# untitled.net
KiCad netlist of a schematic drawn in EAGLE
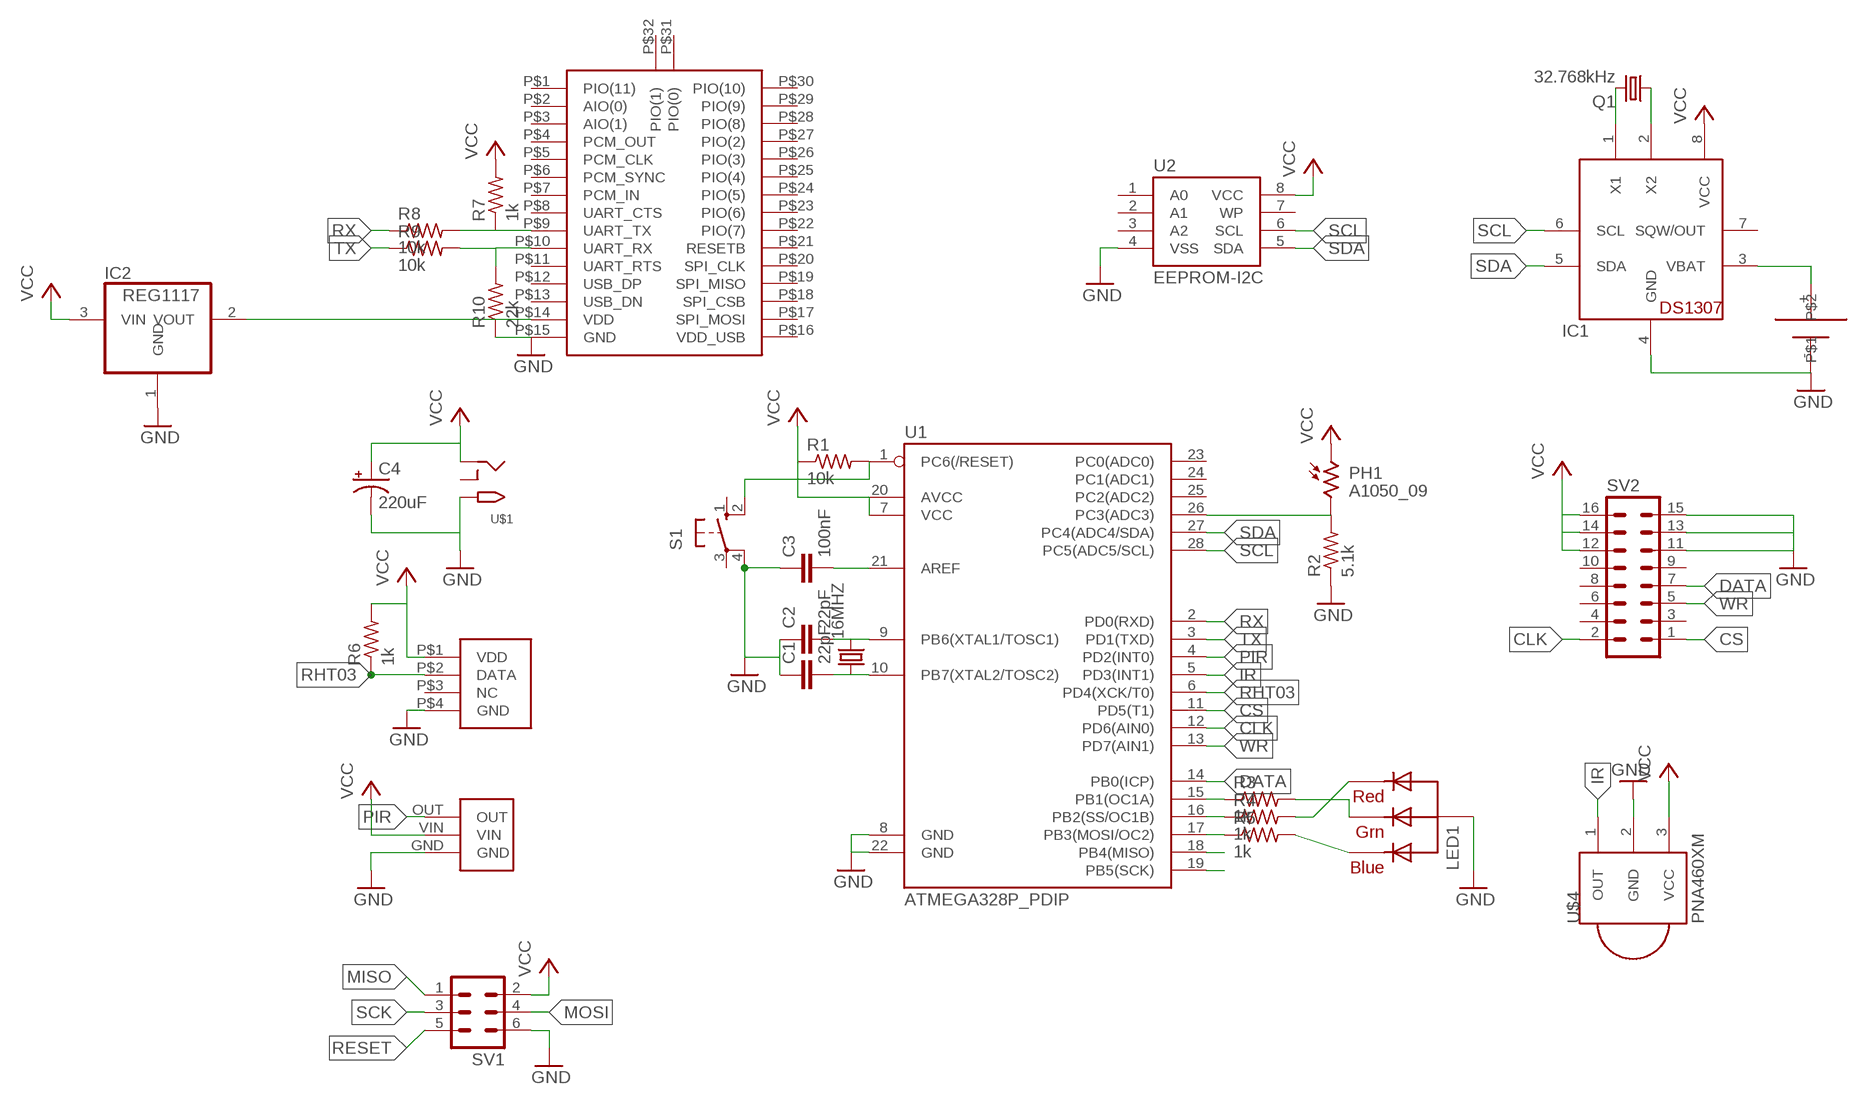
[diagram p0: schematic, sheet 1]

(export (version "E")
  (design (tool "Eeschema 10.0.6"))
  (components
    (comp (ref "16MHZ")
      (value "CRYSTALHC49U-H")
      (footprint "eagle-import:HC49U-H")
      (libsource (lib "eagle-import") (part "CRYSTALHC49U-H"))
    )
    (comp (ref "C1")
      (value "22pF")
      (footprint "eagle-import:C025-024X044")
      (libsource (lib "eagle-import") (part "C-EU025-024X044"))
    )
    (comp (ref "C2")
      (value "22pF")
      (footprint "eagle-import:C025-024X044")
      (libsource (lib "eagle-import") (part "C-EU025-024X044"))
    )
    (comp (ref "C3")
      (value "100nF")
      (footprint "eagle-import:C025-024X044")
      (libsource (lib "eagle-import") (part "C-EU025-024X044"))
    )
    (comp (ref "C4")
      (value "220uF")
      (footprint "eagle-import:E3,5-8")
      (libsource (lib "eagle-import") (part "CPOL-USE3.5-8"))
    )
    (comp (ref "IC1")
      (value "DS1307")
      (footprint "eagle-import:DIL08")
      (libsource (lib "eagle-import") (part "DS1307"))
    )
    (comp (ref "IC2")
      (value "REG1117")
      (footprint "eagle-import:SOT223")
      (libsource (lib "eagle-import") (part "REG1117"))
    )
    (comp (ref "LED1")
      (value "RGBLED_CA-5MM")
      (footprint "eagle-import:LED5MMRGB")
      (libsource (lib "eagle-import") (part "RGBLED_CA-5MM"))
    )
    (comp (ref "PH1")
      (value "A1050_09")
      (footprint "eagle-import:T0-46-A10XX")
      (libsource (lib "eagle-import") (part "A1050_09"))
    )
    (comp (ref "Q1")
      (value "32.768kHz")
      (footprint "eagle-import:TC38H")
      (libsource (lib "eagle-import") (part "CRYSTALTC38H"))
    )
    (comp (ref "R1")
      (value "10k")
      (footprint "eagle-import:0207_10")
      (libsource (lib "eagle-import") (part "R-US_0207/10"))
    )
    (comp (ref "R2")
      (value "5.1k")
      (footprint "eagle-import:0207_10")
      (libsource (lib "eagle-import") (part "R-US_0207/10"))
    )
    (comp (ref "R3")
      (value "1k")
      (footprint "eagle-import:0207_10")
      (libsource (lib "eagle-import") (part "R-US_0207/10"))
    )
    (comp (ref "R4")
      (value "1k")
      (footprint "eagle-import:0207_10")
      (libsource (lib "eagle-import") (part "R-US_0207/10"))
    )
    (comp (ref "R5")
      (value "1k")
      (footprint "eagle-import:0207_10")
      (libsource (lib "eagle-import") (part "R-US_0207/10"))
    )
    (comp (ref "R6")
      (value "1k")
      (footprint "eagle-import:0207_10")
      (libsource (lib "eagle-import") (part "R-US_0207/10"))
    )
    (comp (ref "R7")
      (value "1k")
      (footprint "eagle-import:0207_10")
      (libsource (lib "eagle-import") (part "R-US_0207/10"))
    )
    (comp (ref "R8")
      (value "10k")
      (footprint "eagle-import:0207_10")
      (libsource (lib "eagle-import") (part "R-US_0207/10"))
    )
    (comp (ref "R9")
      (value "10k")
      (footprint "eagle-import:0207_10")
      (libsource (lib "eagle-import") (part "R-US_0207/10"))
    )
    (comp (ref "R10")
      (value "22k")
      (footprint "eagle-import:0207_10")
      (libsource (lib "eagle-import") (part "R-US_0207/10"))
    )
    (comp (ref "S1")
      (value "10-XX")
      (footprint "eagle-import:B3F-10XX")
      (fields (field (name "MPN") "B3F-1000"))
      (libsource (lib "eagle-import") (part "10-XX"))
    )
    (comp (ref "SV1")
      (value "ML6")
      (footprint "eagle-import:ML6")
      (libsource (lib "eagle-import") (part "ML6"))
    )
    (comp (ref "SV2")
      (value "ML16")
      (footprint "eagle-import:ML16")
      (libsource (lib "eagle-import") (part "ML16"))
    )
    (comp (ref "U$1")
      (value "2.1MMJACK")
      (footprint "eagle-import:2.1MMJACK_BREADBOARD")
      (libsource (lib "eagle-import") (part "2.1MMJACK"))
    )
    (comp (ref "U$2")
      (value "RHT03THROUGH_HOLE")
      (footprint "eagle-import:RHT03")
      (libsource (lib "eagle-import") (part "RHT03THROUGH_HOLE"))
    )
    (comp (ref "U$3")
      (value "PIR_PM-6")
      (footprint "eagle-import:PIR_THROUGHHOLE")
      (libsource (lib "eagle-import") (part "PIR_PM-6"))
    )
    (comp (ref "U$4")
      (value "PNA460XM")
      (footprint "eagle-import:PNA460XM")
      (libsource (lib "eagle-import") (part "PNA460XM"))
    )
    (comp (ref "U$5")
      (value "CR2032")
      (footprint "eagle-import:CR2032-THM")
      (libsource (lib "eagle-import") (part "CR2032"))
    )
    (comp (ref "U$6")
      (value "BTM-182")
      (footprint "eagle-import:BTM-182")
      (libsource (lib "eagle-import") (part "BTM-182"))
    )
    (comp (ref "U1")
      (value "ATMEGA328P_PDIP")
      (footprint "eagle-import:DIL28-3")
      (libsource (lib "eagle-import") (part "ATMEGA328P_PDIP"))
    )
    (comp (ref "U2")
      (value "EEPROM-I2C")
      (footprint "eagle-import:DIL08")
      (libsource (lib "eagle-import") (part "EEPROM-I2C"))
    )
  )
  (nets
    (net (code "1") (name "CLK") (class "Default")
      (node (ref "SV2") (pin "2") (pinfunction "2_2") (pintype "passive"))
      (node (ref "U1") (pin "12") (pinfunction "PD6(AIN0)_12") (pintype "bidirectional"))
    )
    (net (code "2") (name "CS") (class "Default")
      (node (ref "SV2") (pin "1") (pinfunction "1_1") (pintype "passive"))
      (node (ref "U1") (pin "11") (pinfunction "PD5(T1)_11") (pintype "bidirectional"))
    )
    (net (code "3") (name "DATA") (class "Default")
      (node (ref "SV2") (pin "7") (pinfunction "7_7") (pintype "passive"))
      (node (ref "U1") (pin "14") (pinfunction "PB0(ICP)_14") (pintype "bidirectional"))
    )
    (net (code "4") (name "GND") (class "Default")
      (node (ref "C1") (pin "1") (pinfunction "1_1") (pintype "passive"))
      (node (ref "C2") (pin "1") (pinfunction "1_1") (pintype "passive"))
      (node (ref "C3") (pin "1") (pinfunction "1_1") (pintype "passive"))
      (node (ref "C4") (pin "-") (pinfunction "-_-") (pintype "passive"))
      (node (ref "IC1") (pin "4") (pinfunction "GND_4") (pintype "power_in"))
      (node (ref "IC2") (pin "1") (pinfunction "GND_1") (pintype "power_in"))
      (node (ref "LED1") (pin "2") (pinfunction "VCC_2") (pintype "bidirectional"))
      (node (ref "R10") (pin "1") (pinfunction "1_1") (pintype "passive"))
      (node (ref "R2") (pin "1") (pinfunction "1_1") (pintype "passive"))
      (node (ref "S1") (pin "4") (pinfunction "P1_4") (pintype "passive"))
      (node (ref "SV1") (pin "6") (pinfunction "6_6") (pintype "passive"))
      (node (ref "SV2") (pin "11") (pinfunction "11_11") (pintype "passive"))
      (node (ref "SV2") (pin "13") (pinfunction "13_13") (pintype "passive"))
      (node (ref "SV2") (pin "15") (pinfunction "15_15") (pintype "passive"))
      (node (ref "U$1") (pin "GND") (pinfunction "TIP_GND") (pintype "bidirectional"))
      (node (ref "U$2") (pin "P$4") (pinfunction "GND_P$4") (pintype "bidirectional"))
      (node (ref "U$3") (pin "GND") (pinfunction "GND_GND") (pintype "bidirectional"))
      (node (ref "U$4") (pin "2") (pinfunction "GND_2") (pintype "power_in"))
      (node (ref "U$5") (pin "-") (pinfunction "P$2_-") (pintype "bidirectional"))
      (node (ref "U$6") (pin "P$15") (pinfunction "GND_P$15") (pintype "bidirectional"))
      (node (ref "U1") (pin "22") (pinfunction "GND_22") (pintype "bidirectional"))
      (node (ref "U1") (pin "8") (pinfunction "GND_8") (pintype "bidirectional"))
      (node (ref "U2") (pin "4") (pinfunction "VSS_4") (pintype "power_in"))
    )
    (net (code "5") (name "IR") (class "Default")
      (node (ref "U$4") (pin "1") (pinfunction "OUT_1") (pintype "output"))
      (node (ref "U1") (pin "5") (pinfunction "PD3(INT1)_5") (pintype "bidirectional"))
    )
    (net (code "6") (name "MISO") (class "Default")
      (node (ref "SV1") (pin "1") (pinfunction "1_1") (pintype "passive"))
      (node (ref "U1") (pin "18") (pinfunction "PB4(MISO)_18") (pintype "bidirectional"))
    )
    (net (code "7") (name "MOSI") (class "Default")
      (node (ref "R5") (pin "1") (pinfunction "1_1") (pintype "passive"))
      (node (ref "SV1") (pin "4") (pinfunction "4_4") (pintype "passive"))
      (node (ref "U1") (pin "17") (pinfunction "PB3(MOSI/OC2)_17") (pintype "bidirectional"))
    )
    (net (code "8") (name "Net-(IC1-VBAT)") (class "Default")
      (node (ref "IC1") (pin "3") (pinfunction "VBAT_3") (pintype "power_in"))
      (node (ref "U$5") (pin "+") (pinfunction "P$1_+") (pintype "bidirectional"))
    )
    (net (code "9") (name "Net-(IC1-X1)") (class "Default")
      (node (ref "IC1") (pin "1") (pinfunction "X1_1") (pintype "passive"))
      (node (ref "Q1") (pin "2") (pinfunction "2_2") (pintype "passive"))
    )
    (net (code "10") (name "Net-(IC1-X2)") (class "Default")
      (node (ref "IC1") (pin "2") (pinfunction "X2_2") (pintype "passive"))
      (node (ref "Q1") (pin "1") (pinfunction "1_1") (pintype "passive"))
    )
    (net (code "11") (name "Net-(IC2-VOUT)") (class "Default")
      (node (ref "IC2") (pin "2") (pinfunction "VOUT_2") (pintype "output"))
      (node (ref "U$6") (pin "P$14") (pinfunction "VDD_P$14") (pintype "bidirectional"))
    )
    (net (code "12") (name "Net-(LED1-BLUE)") (class "Default")
      (node (ref "LED1") (pin "4") (pinfunction "BLUE_4") (pintype "bidirectional"))
      (node (ref "R5") (pin "2") (pinfunction "2_2") (pintype "passive"))
    )
    (net (code "13") (name "Net-(LED1-GREEN)") (class "Default")
      (node (ref "LED1") (pin "3") (pinfunction "GREEN_3") (pintype "bidirectional"))
      (node (ref "R3") (pin "2") (pinfunction "2_2") (pintype "passive"))
    )
    (net (code "14") (name "Net-(LED1-RED)") (class "Default")
      (node (ref "LED1") (pin "1") (pinfunction "RED_1") (pintype "bidirectional"))
      (node (ref "R4") (pin "2") (pinfunction "2_2") (pintype "passive"))
    )
    (net (code "15") (name "Net-(U$6-UART_RX)") (class "Default")
      (node (ref "R10") (pin "2") (pinfunction "2_2") (pintype "passive"))
      (node (ref "R9") (pin "2") (pinfunction "2_2") (pintype "passive"))
      (node (ref "U$6") (pin "P$10") (pinfunction "UART_RX_P$10") (pintype "bidirectional"))
    )
    (net (code "16") (name "Net-(U$6-UART_TX)") (class "Default")
      (node (ref "R7") (pin "1") (pinfunction "1_1") (pintype "passive"))
      (node (ref "R8") (pin "2") (pinfunction "2_2") (pintype "passive"))
      (node (ref "U$6") (pin "P$9") (pinfunction "UART_TX_P$9") (pintype "bidirectional"))
    )
    (net (code "17") (name "Net-(U1-AREF)") (class "Default")
      (node (ref "C3") (pin "2") (pinfunction "2_2") (pintype "passive"))
      (node (ref "U1") (pin "21") (pinfunction "AREF_21") (pintype "bidirectional"))
    )
    (net (code "18") (name "Net-(U1-PB1(OC1A))") (class "Default")
      (node (ref "R3") (pin "1") (pinfunction "1_1") (pintype "passive"))
      (node (ref "U1") (pin "15") (pinfunction "PB1(OC1A)_15") (pintype "bidirectional"))
    )
    (net (code "19") (name "Net-(U1-PB2(SS{slash}OC1B))") (class "Default")
      (node (ref "R4") (pin "1") (pinfunction "1_1") (pintype "passive"))
      (node (ref "U1") (pin "16") (pinfunction "PB2(SS/OC1B)_16") (pintype "bidirectional"))
    )
    (net (code "20") (name "Net-(U1-PB6(XTAL1{slash}TOSC1))") (class "Default")
      (node (ref "16MHZ") (pin "2") (pinfunction "2_2") (pintype "passive"))
      (node (ref "C2") (pin "2") (pinfunction "2_2") (pintype "passive"))
      (node (ref "U1") (pin "9") (pinfunction "PB6(XTAL1/TOSC1)_9") (pintype "bidirectional"))
    )
    (net (code "21") (name "Net-(U1-PB7(XTAL2{slash}TOSC2))") (class "Default")
      (node (ref "16MHZ") (pin "1") (pinfunction "1_1") (pintype "passive"))
      (node (ref "C1") (pin "2") (pinfunction "2_2") (pintype "passive"))
      (node (ref "U1") (pin "10") (pinfunction "PB7(XTAL2/TOSC2)_10") (pintype "bidirectional"))
    )
    (net (code "22") (name "Net-(U1-PC3(ADC3))") (class "Default")
      (node (ref "PH1") (pin "2") (pinfunction "2_2") (pintype "passive"))
      (node (ref "R2") (pin "2") (pinfunction "2_2") (pintype "passive"))
      (node (ref "U1") (pin "26") (pinfunction "PC3(ADC3)_26") (pintype "bidirectional"))
    )
    (net (code "23") (name "PIR") (class "Default")
      (node (ref "U$3") (pin "OUT") (pinfunction "OUT_OUT") (pintype "bidirectional"))
      (node (ref "U1") (pin "4") (pinfunction "PD2(INT0)_4") (pintype "bidirectional"))
    )
    (net (code "24") (name "RESET") (class "Default")
      (node (ref "R1") (pin "2") (pinfunction "2_2") (pintype "passive"))
      (node (ref "S1") (pin "2") (pinfunction "S1_2") (pintype "passive"))
      (node (ref "SV1") (pin "5") (pinfunction "5_5") (pintype "passive"))
      (node (ref "U1") (pin "1") (pinfunction "PC6(/RESET)_1") (pintype "bidirectional"))
    )
    (net (code "25") (name "RHT03") (class "Default")
      (node (ref "R6") (pin "1") (pinfunction "1_1") (pintype "passive"))
      (node (ref "U$2") (pin "P$2") (pinfunction "DATA_P$2") (pintype "bidirectional"))
      (node (ref "U1") (pin "6") (pinfunction "PD4(XCK/T0)_6") (pintype "bidirectional"))
    )
    (net (code "26") (name "RX") (class "Default")
      (node (ref "R8") (pin "1") (pinfunction "1_1") (pintype "passive"))
      (node (ref "U1") (pin "2") (pinfunction "PD0(RXD)_2") (pintype "bidirectional"))
    )
    (net (code "27") (name "SCK") (class "Default")
      (node (ref "SV1") (pin "3") (pinfunction "3_3") (pintype "passive"))
      (node (ref "U1") (pin "19") (pinfunction "PB5(SCK)_19") (pintype "bidirectional"))
    )
    (net (code "28") (name "SCL") (class "Default")
      (node (ref "IC1") (pin "6") (pinfunction "SCL_6") (pintype "bidirectional"))
      (node (ref "U1") (pin "28") (pinfunction "PC5(ADC5/SCL)_28") (pintype "bidirectional"))
      (node (ref "U2") (pin "6") (pinfunction "SCL_6") (pintype "bidirectional"))
    )
    (net (code "29") (name "SDA") (class "Default")
      (node (ref "IC1") (pin "5") (pinfunction "SDA_5") (pintype "bidirectional"))
      (node (ref "U1") (pin "27") (pinfunction "PC4(ADC4/SDA)_27") (pintype "bidirectional"))
      (node (ref "U2") (pin "5") (pinfunction "SDA_5") (pintype "bidirectional"))
    )
    (net (code "30") (name "TX") (class "Default")
      (node (ref "R9") (pin "1") (pinfunction "1_1") (pintype "passive"))
      (node (ref "U1") (pin "3") (pinfunction "PD1(TXD)_3") (pintype "bidirectional"))
    )
    (net (code "31") (name "VCC") (class "Default")
      (node (ref "C4") (pin "+") (pinfunction "+_+") (pintype "passive"))
      (node (ref "IC1") (pin "8") (pinfunction "VCC_8") (pintype "power_in"))
      (node (ref "IC2") (pin "3") (pinfunction "VIN_3") (pintype "input"))
      (node (ref "PH1") (pin "1") (pinfunction "1_1") (pintype "passive"))
      (node (ref "R1") (pin "1") (pinfunction "1_1") (pintype "passive"))
      (node (ref "R6") (pin "2") (pinfunction "2_2") (pintype "passive"))
      (node (ref "R7") (pin "2") (pinfunction "2_2") (pintype "passive"))
      (node (ref "SV1") (pin "2") (pinfunction "2_2") (pintype "passive"))
      (node (ref "SV2") (pin "12") (pinfunction "12_12") (pintype "passive"))
      (node (ref "SV2") (pin "14") (pinfunction "14_14") (pintype "passive"))
      (node (ref "SV2") (pin "16") (pinfunction "16_16") (pintype "passive"))
      (node (ref "U$1") (pin "PWR") (pinfunction "RING_PWR") (pintype "bidirectional"))
      (node (ref "U$2") (pin "P$1") (pinfunction "VDD_P$1") (pintype "bidirectional"))
      (node (ref "U$3") (pin "VIN") (pinfunction "VIN_VIN") (pintype "bidirectional"))
      (node (ref "U$4") (pin "3") (pinfunction "VCC_3") (pintype "power_in"))
      (node (ref "U1") (pin "20") (pinfunction "AVCC_20") (pintype "bidirectional"))
      (node (ref "U1") (pin "7") (pinfunction "VCC_7") (pintype "bidirectional"))
      (node (ref "U2") (pin "8") (pinfunction "VCC_8") (pintype "power_in"))
    )
    (net (code "32") (name "WR") (class "Default")
      (node (ref "SV2") (pin "5") (pinfunction "5_5") (pintype "passive"))
      (node (ref "U1") (pin "13") (pinfunction "PD7(AIN1)_13") (pintype "bidirectional"))
    )
    (net (code "33") (name "unconnected-(IC1-SQW{slash}OUT-Pad7)") (class "Default")
      (node (ref "IC1") (pin "7") (pinfunction "SQW/OUT_7") (pintype "bidirectional"))
    )
    (net (code "34") (name "unconnected-(S1-P-Pad3)") (class "Default")
      (node (ref "S1") (pin "3") (pinfunction "P_3") (pintype "passive"))
    )
    (net (code "35") (name "unconnected-(S1-S-Pad1)") (class "Default")
      (node (ref "S1") (pin "1") (pinfunction "S_1") (pintype "passive"))
    )
    (net (code "36") (name "unconnected-(SV2-Pad3)") (class "Default")
      (node (ref "SV2") (pin "3") (pinfunction "3_3") (pintype "passive"))
    )
    (net (code "37") (name "unconnected-(SV2-Pad4)") (class "Default")
      (node (ref "SV2") (pin "4") (pinfunction "4_4") (pintype "passive"))
    )
    (net (code "38") (name "unconnected-(SV2-Pad6)") (class "Default")
      (node (ref "SV2") (pin "6") (pinfunction "6_6") (pintype "passive"))
    )
    (net (code "39") (name "unconnected-(SV2-Pad8)") (class "Default")
      (node (ref "SV2") (pin "8") (pinfunction "8_8") (pintype "passive"))
    )
    (net (code "40") (name "unconnected-(SV2-Pad9)") (class "Default")
      (node (ref "SV2") (pin "9") (pinfunction "9_9") (pintype "passive"))
    )
    (net (code "41") (name "unconnected-(SV2-Pad10)") (class "Default")
      (node (ref "SV2") (pin "10") (pinfunction "10_10") (pintype "passive"))
    )
    (net (code "42") (name "unconnected-(U$1-RING_SW-PadGNDBREAK)") (class "Default")
      (node (ref "U$1") (pin "GNDBREAK") (pinfunction "RING_SW_GNDBREAK") (pintype "bidirectional"))
    )
    (net (code "43") (name "unconnected-(U$2-NC-PadP$3)") (class "Default")
      (node (ref "U$2") (pin "P$3") (pinfunction "NC_P$3") (pintype "bidirectional"))
    )
    (net (code "44") (name "unconnected-(U$6-AIO(0)-PadP$2)") (class "Default")
      (node (ref "U$6") (pin "P$2") (pinfunction "AIO(0)_P$2") (pintype "bidirectional"))
    )
    (net (code "45") (name "unconnected-(U$6-AIO(1)-PadP$3)") (class "Default")
      (node (ref "U$6") (pin "P$3") (pinfunction "AIO(1)_P$3") (pintype "bidirectional"))
    )
    (net (code "46") (name "unconnected-(U$6-PCM_CLK-PadP$5)") (class "Default")
      (node (ref "U$6") (pin "P$5") (pinfunction "PCM_CLK_P$5") (pintype "bidirectional"))
    )
    (net (code "47") (name "unconnected-(U$6-PCM_IN-PadP$7)") (class "Default")
      (node (ref "U$6") (pin "P$7") (pinfunction "PCM_IN_P$7") (pintype "bidirectional"))
    )
    (net (code "48") (name "unconnected-(U$6-PCM_OUT-PadP$4)") (class "Default")
      (node (ref "U$6") (pin "P$4") (pinfunction "PCM_OUT_P$4") (pintype "bidirectional"))
    )
    (net (code "49") (name "unconnected-(U$6-PCM_SYNC-PadP$6)") (class "Default")
      (node (ref "U$6") (pin "P$6") (pinfunction "PCM_SYNC_P$6") (pintype "bidirectional"))
    )
    (net (code "50") (name "unconnected-(U$6-PIO(0)-PadP$31)") (class "Default")
      (node (ref "U$6") (pin "P$31") (pinfunction "PIO(0)_P$31") (pintype "bidirectional"))
    )
    (net (code "51") (name "unconnected-(U$6-PIO(1)-PadP$32)") (class "Default")
      (node (ref "U$6") (pin "P$32") (pinfunction "PIO(1)_P$32") (pintype "bidirectional"))
    )
    (net (code "52") (name "unconnected-(U$6-PIO(2)-PadP$27)") (class "Default")
      (node (ref "U$6") (pin "P$27") (pinfunction "PIO(2)_P$27") (pintype "bidirectional"))
    )
    (net (code "53") (name "unconnected-(U$6-PIO(3)-PadP$26)") (class "Default")
      (node (ref "U$6") (pin "P$26") (pinfunction "PIO(3)_P$26") (pintype "bidirectional"))
    )
    (net (code "54") (name "unconnected-(U$6-PIO(4)-PadP$25)") (class "Default")
      (node (ref "U$6") (pin "P$25") (pinfunction "PIO(4)_P$25") (pintype "bidirectional"))
    )
    (net (code "55") (name "unconnected-(U$6-PIO(5)-PadP$24)") (class "Default")
      (node (ref "U$6") (pin "P$24") (pinfunction "PIO(5)_P$24") (pintype "bidirectional"))
    )
    (net (code "56") (name "unconnected-(U$6-PIO(6)-PadP$23)") (class "Default")
      (node (ref "U$6") (pin "P$23") (pinfunction "PIO(6)_P$23") (pintype "bidirectional"))
    )
    (net (code "57") (name "unconnected-(U$6-PIO(7)-PadP$22)") (class "Default")
      (node (ref "U$6") (pin "P$22") (pinfunction "PIO(7)_P$22") (pintype "bidirectional"))
    )
    (net (code "58") (name "unconnected-(U$6-PIO(8)-PadP$28)") (class "Default")
      (node (ref "U$6") (pin "P$28") (pinfunction "PIO(8)_P$28") (pintype "bidirectional"))
    )
    (net (code "59") (name "unconnected-(U$6-PIO(9)-PadP$29)") (class "Default")
      (node (ref "U$6") (pin "P$29") (pinfunction "PIO(9)_P$29") (pintype "bidirectional"))
    )
    (net (code "60") (name "unconnected-(U$6-PIO(10)-PadP$30)") (class "Default")
      (node (ref "U$6") (pin "P$30") (pinfunction "PIO(10)_P$30") (pintype "bidirectional"))
    )
    (net (code "61") (name "unconnected-(U$6-PIO(11)-PadP$1)") (class "Default")
      (node (ref "U$6") (pin "P$1") (pinfunction "PIO(11)_P$1") (pintype "bidirectional"))
    )
    (net (code "62") (name "unconnected-(U$6-RESETB-PadP$21)") (class "Default")
      (node (ref "U$6") (pin "P$21") (pinfunction "RESETB_P$21") (pintype "bidirectional"))
    )
    (net (code "63") (name "unconnected-(U$6-SPI_CLK-PadP$20)") (class "Default")
      (node (ref "U$6") (pin "P$20") (pinfunction "SPI_CLK_P$20") (pintype "bidirectional"))
    )
    (net (code "64") (name "unconnected-(U$6-SPI_CSB-PadP$18)") (class "Default")
      (node (ref "U$6") (pin "P$18") (pinfunction "SPI_CSB_P$18") (pintype "bidirectional"))
    )
    (net (code "65") (name "unconnected-(U$6-SPI_MISO-PadP$19)") (class "Default")
      (node (ref "U$6") (pin "P$19") (pinfunction "SPI_MISO_P$19") (pintype "bidirectional"))
    )
    (net (code "66") (name "unconnected-(U$6-SPI_MOSI-PadP$17)") (class "Default")
      (node (ref "U$6") (pin "P$17") (pinfunction "SPI_MOSI_P$17") (pintype "bidirectional"))
    )
    (net (code "67") (name "unconnected-(U$6-UART_CTS-PadP$8)") (class "Default")
      (node (ref "U$6") (pin "P$8") (pinfunction "UART_CTS_P$8") (pintype "bidirectional"))
    )
    (net (code "68") (name "unconnected-(U$6-UART_RTS-PadP$11)") (class "Default")
      (node (ref "U$6") (pin "P$11") (pinfunction "UART_RTS_P$11") (pintype "bidirectional"))
    )
    (net (code "69") (name "unconnected-(U$6-USB_DN-PadP$13)") (class "Default")
      (node (ref "U$6") (pin "P$13") (pinfunction "USB_DN_P$13") (pintype "bidirectional"))
    )
    (net (code "70") (name "unconnected-(U$6-USB_DP-PadP$12)") (class "Default")
      (node (ref "U$6") (pin "P$12") (pinfunction "USB_DP_P$12") (pintype "bidirectional"))
    )
    (net (code "71") (name "unconnected-(U$6-VDD_USB-PadP$16)") (class "Default")
      (node (ref "U$6") (pin "P$16") (pinfunction "VDD_USB_P$16") (pintype "bidirectional"))
    )
    (net (code "72") (name "unconnected-(U1-PC0(ADC0)-Pad23)") (class "Default")
      (node (ref "U1") (pin "23") (pinfunction "PC0(ADC0)_23") (pintype "bidirectional"))
    )
    (net (code "73") (name "unconnected-(U1-PC1(ADC1)-Pad24)") (class "Default")
      (node (ref "U1") (pin "24") (pinfunction "PC1(ADC1)_24") (pintype "bidirectional"))
    )
    (net (code "74") (name "unconnected-(U1-PC2(ADC2)-Pad25)") (class "Default")
      (node (ref "U1") (pin "25") (pinfunction "PC2(ADC2)_25") (pintype "bidirectional"))
    )
    (net (code "75") (name "unconnected-(U2-A0-Pad1)") (class "Default")
      (node (ref "U2") (pin "1") (pinfunction "A0_1") (pintype "bidirectional"))
    )
    (net (code "76") (name "unconnected-(U2-A1-Pad2)") (class "Default")
      (node (ref "U2") (pin "2") (pinfunction "A1_2") (pintype "bidirectional"))
    )
    (net (code "77") (name "unconnected-(U2-A2-Pad3)") (class "Default")
      (node (ref "U2") (pin "3") (pinfunction "A2_3") (pintype "bidirectional"))
    )
    (net (code "78") (name "unconnected-(U2-WP-Pad7)") (class "Default")
      (node (ref "U2") (pin "7") (pinfunction "WP_7") (pintype "bidirectional"))
    )
  )
)
